# design.net
KiCad netlist of a schematic drawn in Altium Designer
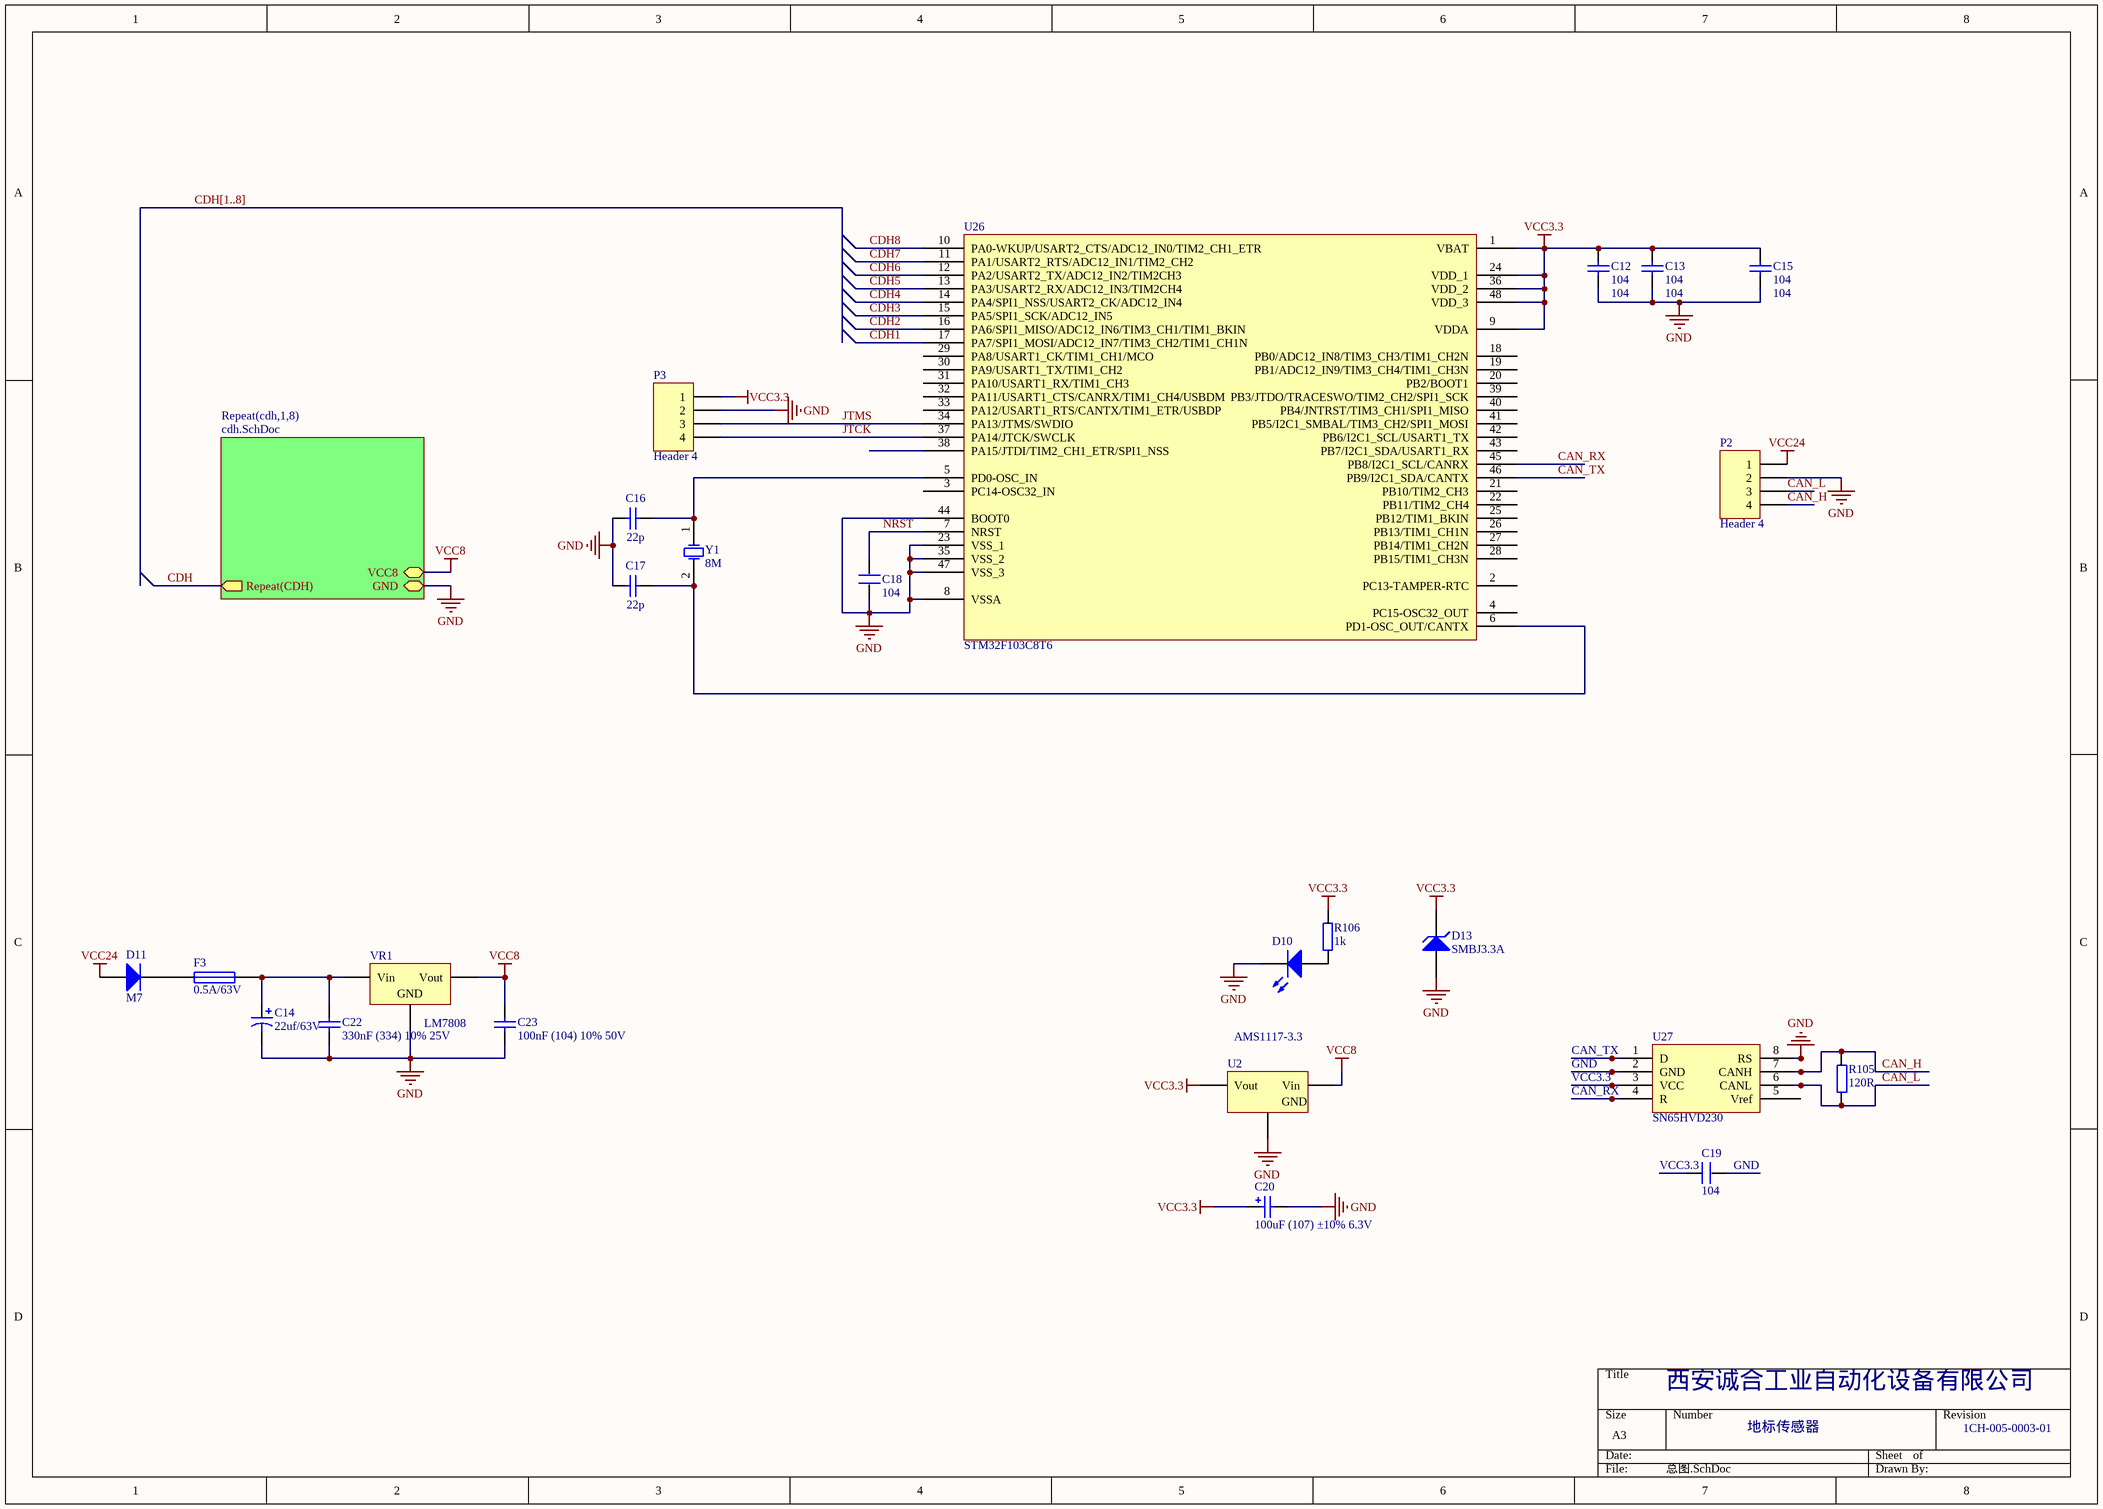
[diagram p0: 总图.SchDoc]

(export (version "E")
  (design (tool "Eeschema 10.0.6"))
  (components
    (comp (ref "C12")
      (value "104")
      (footprint "0603-CAP")
      (description "Capacitor")
      (fields (field (name "ALTIUM_VALUE") "104") (field (name "PUBLISHER") "Altium Limited"))
      (libsource (lib "Miscellaneous Devices") (part "Cap"))
    )
    (comp (ref "C13")
      (value "104")
      (footprint "0603-CAP")
      (description "Capacitor")
      (fields (field (name "ALTIUM_VALUE") "104") (field (name "PUBLISHER") "Altium Limited"))
      (libsource (lib "Miscellaneous Devices") (part "Cap"))
    )
    (comp (ref "C14")
      (value "22uf/63V")
      (footprint "CAP-6*12")
      (description "Polarized Capacitor (Surface Mount)")
      (fields (field (name "PUBLISHER") "Altium Limited"))
      (libsource (lib "Miscellaneous Devices") (part "Cap Pol3"))
    )
    (comp (ref "C15")
      (value "104")
      (footprint "0603-CAP")
      (description "Capacitor")
      (fields (field (name "ALTIUM_VALUE") "104") (field (name "PUBLISHER") "Altium Limited"))
      (libsource (lib "Miscellaneous Devices") (part "Cap"))
    )
    (comp (ref "C16")
      (value "22p")
      (footprint "0603-CAP")
      (description "Capacitor")
      (fields (field (name "PUBLISHER") "Altium Limited"))
      (libsource (lib "Miscellaneous Devices") (part "Cap"))
    )
    (comp (ref "C17")
      (value "22p")
      (footprint "0603-CAP")
      (description "Capacitor")
      (fields (field (name "PUBLISHER") "Altium Limited"))
      (libsource (lib "Miscellaneous Devices") (part "Cap"))
    )
    (comp (ref "C18")
      (value "104")
      (footprint "0603-CAP")
      (libsource (lib "Explorer STM32F407封装库") (part "C"))
    )
    (comp (ref "C19")
      (value "104")
      (footprint "0603-CAP")
      (libsource (lib "Explorer STM32F407封装库") (part "C_3"))
    )
    (comp (ref "C20")
      (value "100uF (107) ±10% 6.3V")
      (footprint "CASE-B_3528")
      (description "钽电容")
      (libsource (lib "Miscellaneous Devices LC") (part "3528 100uF (107) 10% 6.3V"))
    )
    (comp (ref "C22")
      (value "330nF (334) 10% 25V")
      (footprint "0603_C")
      (description "贴片电容")
      (libsource (lib "Miscellaneous Devices LC") (part "0603 330nF (334) 10% 25V"))
    )
    (comp (ref "C23")
      (value "100nF (104) 10% 50V")
      (footprint "0603_C")
      (description "贴片电容")
      (libsource (lib "Miscellaneous Devices LC") (part "0603 100nF (104) 10% 50V"))
    )
    (comp (ref "D10")
      (value "LED0")
      (footprint "LC-0805_LED_S1")
      (description "Typical INFRARED GaAs LED")
      (fields (field (name "PUBLISHER") "Altium Limited"))
      (libsource (lib "继电器板_1") (part "LED0"))
    )
    (comp (ref "D11")
      (value "M7")
      (footprint "SMA(DO-214AC)_S1")
      (description "二极管")
      (libsource (lib "Miscellaneous Devices LC") (part "SMA(DO-214AC) M7"))
    )
    (comp (ref "D13")
      (value "SMBJ3.3A")
      (footprint "SMB(DO-214AA)_S1")
      (description "Zener Diode")
      (fields (field (name "PUBLISHER") "Altium Limited"))
      (libsource (lib "Miscellaneous Devices") (part "D Zener"))
    )
    (comp (ref "F3")
      (value "0.5A/63V")
      (footprint "1206")
      (description "Fuse")
      (fields (field (name "PUBLISHER") "Altium Limited"))
      (libsource (lib "Miscellaneous Devices") (part "Fuse 1"))
    )
    (comp (ref "P2")
      (value "Header 4")
      (footprint "DZ-4-3.5")
      (description "Header, 4-Pin")
      (fields (field (name "PUBLISHER") "Altium Limited"))
      (libsource (lib "Miscellaneous Connectors") (part "Header 4"))
    )
    (comp (ref "P3")
      (value "Header 4")
      (footprint "HDR1X4")
      (description "Header, 4-Pin")
      (fields (field (name "PUBLISHER") "Altium Limited"))
      (libsource (lib "Miscellaneous Connectors") (part "Header 4"))
    )
    (comp (ref "R105")
      (value "120R")
      (footprint "0603")
      (libsource (lib "Explorer STM32F407封装库") (part "R_2"))
    )
    (comp (ref "R106") (value "1k") (footprint "0603") (libsource (lib "Explorer STM32F407封装库") (part "R_2")))
    (comp (ref "U2")
      (value "AMS1117-3.3")
      (footprint "SOT-223")
      (description "低压差线性稳压(LDO)")
      (libsource (lib "Miscellaneous Devices LC") (part "SOT-223 AMS1117-3.3"))
    )
    (comp (ref "U26")
      (value "STM32F103C8T6")
      (footprint "LC-LQFP-48")
      (libsource (lib "Schlib1") (part "stm32f103v8t6"))
    )
    (comp (ref "U27")
      (value "SN65HVD230")
      (footprint "SOIC-8_150mil")
      (description "CAN")
      (libsource (lib "Miscellaneous Devices LC") (part "CAN/SN65HVD230DR"))
    )
    (comp (ref "VR1")
      (value "LM7808")
      (footprint "LC-TO-263-2")
      (description "低压差线性稳压(LDO)")
      (libsource (lib "Miscellaneous Devices LC") (part "SOT-89 78L05G-AB3-R"))
    )
    (comp (ref "Y1")
      (value "8M")
      (footprint "XTAL_US1")
      (description "Crystal Oscillator")
      (fields (field (name "PUBLISHER") "Altium Limited"))
      (libsource (lib "Miscellaneous Devices") (part "XTAL"))
    )
  )
  (nets
    (net (code "1") (name "/CAN_H") (class "Default")
      (node (ref "P2") (pin "4") (pinfunction "4_4") (pintype "passive"))
      (node (ref "R105") (pin "2") (pintype "passive"))
      (node (ref "U27") (pin "7") (pinfunction "CANH_7") (pintype "passive"))
    )
    (net (code "2") (name "/CAN_L") (class "Default")
      (node (ref "P2") (pin "3") (pinfunction "3_3") (pintype "passive"))
      (node (ref "R105") (pin "1") (pintype "passive"))
      (node (ref "U27") (pin "6") (pinfunction "CANL_6") (pintype "passive"))
    )
    (net (code "3") (name "/CAN_RX") (class "Default")
      (node (ref "U26") (pin "45") (pinfunction "PB8/I2C1_SCL/CANRX_45") (pintype "passive"))
      (node (ref "U27") (pin "4") (pinfunction "R_4") (pintype "passive"))
    )
    (net (code "4") (name "/CAN_TX") (class "Default")
      (node (ref "U26") (pin "46") (pinfunction "PB9/I2C1_SDA/CANTX_46") (pintype "passive"))
      (node (ref "U27") (pin "1") (pinfunction "D_1") (pintype "passive"))
    )
    (net (code "6") (name "/CDH1") (class "Default")
      (node (ref "U26") (pin "17") (pinfunction "PA7/SPI1_MOSI/ADC12_IN7/TIM3_CH2/TIM1_CH1N_17") (pintype "passive"))
    )
    (net (code "7") (name "/CDH2") (class "Default")
      (node (ref "U26") (pin "16") (pinfunction "PA6/SPI1_MISO/ADC12_IN6/TIM3_CH1/TIM1_BKIN_16") (pintype "passive"))
    )
    (net (code "8") (name "/CDH3") (class "Default")
      (node (ref "U26") (pin "15") (pinfunction "PA5/SPI1_SCK/ADC12_IN5_15") (pintype "passive"))
    )
    (net (code "9") (name "/CDH4") (class "Default")
      (node (ref "U26") (pin "14") (pinfunction "PA4/SPI1_NSS/USART2_CK/ADC12_IN4_14") (pintype "passive"))
    )
    (net (code "10") (name "/CDH5") (class "Default")
      (node (ref "U26") (pin "13") (pinfunction "PA3/USART2_RX/ADC12_IN3/TIM2CH4_13") (pintype "passive"))
    )
    (net (code "11") (name "/CDH6") (class "Default")
      (node (ref "U26") (pin "12") (pinfunction "PA2/USART2_TX/ADC12_IN2/TIM2CH3_12") (pintype "passive"))
    )
    (net (code "12") (name "/CDH7") (class "Default")
      (node (ref "U26") (pin "11") (pinfunction "PA1/USART2_RTS/ADC12_IN1/TIM2_CH2_11") (pintype "passive"))
    )
    (net (code "13") (name "/CDH8") (class "Default")
      (node (ref "U26") (pin "10") (pinfunction "PA0-WKUP/USART2_CTS/ADC12_IN0/TIM2_CH1_ETR_10") (pintype "passive"))
    )
    (net (code "15") (name "/JTCK") (class "Default")
      (node (ref "P3") (pin "4") (pinfunction "4_4") (pintype "passive"))
      (node (ref "U26") (pin "37") (pinfunction "PA14/JTCK/SWCLK_37") (pintype "passive"))
    )
    (net (code "16") (name "/JTMS") (class "Default")
      (node (ref "P3") (pin "3") (pinfunction "3_3") (pintype "passive"))
      (node (ref "U26") (pin "34") (pinfunction "PA13/JTMS/SWDIO_34") (pintype "passive"))
    )
    (net (code "17") (name "/NRST") (class "Default")
      (node (ref "C18") (pin "2") (pintype "passive"))
      (node (ref "U26") (pin "7") (pinfunction "NRST_7") (pintype "passive"))
    )
    (net (code "18") (name "GND") (class "Default")
      (node (ref "C12") (pin "2") (pinfunction "2_2") (pintype "passive"))
      (node (ref "C13") (pin "2") (pinfunction "2_2") (pintype "passive"))
      (node (ref "C14") (pin "2") (pinfunction "2_2") (pintype "passive"))
      (node (ref "C15") (pin "2") (pinfunction "2_2") (pintype "passive"))
      (node (ref "C16") (pin "2") (pinfunction "2_2") (pintype "passive"))
      (node (ref "C17") (pin "2") (pinfunction "2_2") (pintype "passive"))
      (node (ref "C18") (pin "1") (pintype "passive"))
      (node (ref "C19") (pin "2") (pintype "passive"))
      (node (ref "C20") (pin "2") (pinfunction "2_2") (pintype "passive"))
      (node (ref "C22") (pin "1") (pinfunction "1_1") (pintype "passive"))
      (node (ref "C23") (pin "1") (pinfunction "1_1") (pintype "passive"))
      (node (ref "D10") (pin "K") (pinfunction "K_K") (pintype "passive"))
      (node (ref "D13") (pin "1") (pinfunction "A_1") (pintype "passive"))
      (node (ref "P2") (pin "2") (pinfunction "2_2") (pintype "passive"))
      (node (ref "P3") (pin "2") (pinfunction "2_2") (pintype "passive"))
      (node (ref "U2") (pin "1") (pinfunction "GND_1") (pintype "passive"))
      (node (ref "U26") (pin "23") (pinfunction "VSS_1_23") (pintype "passive"))
      (node (ref "U26") (pin "35") (pinfunction "VSS_2_35") (pintype "passive"))
      (node (ref "U26") (pin "44") (pinfunction "BOOT0_44") (pintype "passive"))
      (node (ref "U26") (pin "47") (pinfunction "VSS_3_47") (pintype "passive"))
      (node (ref "U26") (pin "8") (pinfunction "VSSA_8") (pintype "passive"))
      (node (ref "U27") (pin "2") (pinfunction "GND_2") (pintype "passive"))
      (node (ref "U27") (pin "8") (pinfunction "RS_8") (pintype "passive"))
      (node (ref "VR1") (pin "2") (pinfunction "GND_2") (pintype "passive"))
    )
    (net (code "19") (name "Net-(D10-PadA)") (class "Default")
      (node (ref "D10") (pin "A") (pinfunction "A_A") (pintype "passive"))
      (node (ref "R106") (pin "2") (pintype "passive"))
    )
    (net (code "20") (name "Net-(D11-K)") (class "Default")
      (node (ref "D11") (pin "2") (pinfunction "K_2") (pintype "passive"))
      (node (ref "F3") (pin "1") (pinfunction "1_1") (pintype "passive"))
    )
    (net (code "21") (name "Net-(U26-PD0-OSC_IN)") (class "Default")
      (node (ref "C16") (pin "1") (pinfunction "1_1") (pintype "passive"))
      (node (ref "U26") (pin "5") (pinfunction "PD0-OSC_IN_5") (pintype "passive"))
      (node (ref "Y1") (pin "1") (pinfunction "OSC1_1") (pintype "passive"))
    )
    (net (code "22") (name "Net-(U26-PD1-OSC_OUT{slash}CANTX)") (class "Default")
      (node (ref "C17") (pin "1") (pinfunction "1_1") (pintype "passive"))
      (node (ref "U26") (pin "6") (pinfunction "PD1-OSC_OUT/CANTX_6") (pintype "passive"))
      (node (ref "Y1") (pin "2") (pinfunction "OSC2_2") (pintype "passive"))
    )
    (net (code "23") (name "Net-(VR1-Vin)") (class "Default")
      (node (ref "C14") (pin "1") (pinfunction "1_1") (pintype "passive"))
      (node (ref "C22") (pin "2") (pinfunction "2_2") (pintype "passive"))
      (node (ref "F3") (pin "2") (pinfunction "2_2") (pintype "passive"))
      (node (ref "VR1") (pin "1") (pinfunction "Vin_1") (pintype "passive"))
    )
    (net (code "24") (name "VCC3.3") (class "Default")
      (node (ref "C12") (pin "1") (pinfunction "1_1") (pintype "passive"))
      (node (ref "C13") (pin "1") (pinfunction "1_1") (pintype "passive"))
      (node (ref "C15") (pin "1") (pinfunction "1_1") (pintype "passive"))
      (node (ref "C19") (pin "1") (pintype "passive"))
      (node (ref "C20") (pin "1") (pinfunction "1_1") (pintype "passive"))
      (node (ref "D13") (pin "2") (pinfunction "K_2") (pintype "passive"))
      (node (ref "P3") (pin "1") (pinfunction "1_1") (pintype "passive"))
      (node (ref "R106") (pin "1") (pintype "passive"))
      (node (ref "U2") (pin "2") (pinfunction "Vout_2") (pintype "passive"))
      (node (ref "U26") (pin "1") (pinfunction "VBAT_1") (pintype "passive"))
      (node (ref "U26") (pin "24") (pinfunction "VDD_1_24") (pintype "passive"))
      (node (ref "U26") (pin "36") (pinfunction "VDD_2_36") (pintype "passive"))
      (node (ref "U26") (pin "48") (pinfunction "VDD_3_48") (pintype "passive"))
      (node (ref "U26") (pin "9") (pinfunction "VDDA_9") (pintype "passive"))
      (node (ref "U27") (pin "3") (pinfunction "VCC_3") (pintype "passive"))
    )
    (net (code "25") (name "VCC8") (class "Default")
      (node (ref "C23") (pin "2") (pinfunction "2_2") (pintype "passive"))
      (node (ref "U2") (pin "3") (pinfunction "Vin_3") (pintype "passive"))
      (node (ref "VR1") (pin "3") (pinfunction "Vout_3") (pintype "passive"))
    )
    (net (code "26") (name "VCC24") (class "Default")
      (node (ref "D11") (pin "1") (pinfunction "A_1") (pintype "passive"))
      (node (ref "P2") (pin "1") (pinfunction "1_1") (pintype "passive"))
    )
    (net (code "27") (name "unconnected-(U26-PA8{slash}USART1_CK{slash}TIM1_CH1{slash}MCO-Pad29)") (class "Default")
      (node (ref "U26") (pin "29") (pinfunction "PA8/USART1_CK/TIM1_CH1/MCO_29") (pintype "passive"))
    )
    (net (code "28") (name "unconnected-(U26-PA9{slash}USART1_TX{slash}TIM1_CH2-Pad30)") (class "Default")
      (node (ref "U26") (pin "30") (pinfunction "PA9/USART1_TX/TIM1_CH2_30") (pintype "passive"))
    )
    (net (code "29") (name "unconnected-(U26-PA10{slash}USART1_RX{slash}TIM1_CH3-Pad31)") (class "Default")
      (node (ref "U26") (pin "31") (pinfunction "PA10/USART1_RX/TIM1_CH3_31") (pintype "passive"))
    )
    (net (code "30") (name "unconnected-(U26-PA11{slash}USART1_CTS{slash}CANRX{slash}TIM1_CH4{slash}USBDM-Pad32)") (class "Default")
      (node (ref "U26") (pin "32") (pinfunction "PA11/USART1_CTS/CANRX/TIM1_CH4/USBDM_32") (pintype "passive"))
    )
    (net (code "31") (name "unconnected-(U26-PA12{slash}USART1_RTS{slash}CANTX{slash}TIM1_ETR{slash}USBDP-Pad33)") (class "Default")
      (node (ref "U26") (pin "33") (pinfunction "PA12/USART1_RTS/CANTX/TIM1_ETR/USBDP_33") (pintype "passive"))
    )
    (net (code "32") (name "unconnected-(U26-PA15{slash}JTDI{slash}TIM2_CH1_ETR{slash}SPI1_NSS-Pad38)") (class "Default")
      (node (ref "U26") (pin "38") (pinfunction "PA15/JTDI/TIM2_CH1_ETR/SPI1_NSS_38") (pintype "passive"))
    )
    (net (code "33") (name "unconnected-(U26-PB0{slash}ADC12_IN8{slash}TIM3_CH3{slash}TIM1_CH2N-Pad18)") (class "Default")
      (node (ref "U26") (pin "18") (pinfunction "PB0/ADC12_IN8/TIM3_CH3/TIM1_CH2N_18") (pintype "passive"))
    )
    (net (code "34") (name "unconnected-(U26-PB1{slash}ADC12_IN9{slash}TIM3_CH4{slash}TIM1_CH3N-Pad19)") (class "Default")
      (node (ref "U26") (pin "19") (pinfunction "PB1/ADC12_IN9/TIM3_CH4/TIM1_CH3N_19") (pintype "passive"))
    )
    (net (code "35") (name "unconnected-(U26-PB2{slash}BOOT1-Pad20)") (class "Default")
      (node (ref "U26") (pin "20") (pinfunction "PB2/BOOT1_20") (pintype "passive"))
    )
    (net (code "36") (name "unconnected-(U26-PB3{slash}JTDO{slash}TRACESWO{slash}TIM2_CH2{slash}SPI1_SCK-Pad39)") (class "Default")
      (node (ref "U26") (pin "39") (pinfunction "PB3/JTDO/TRACESWO/TIM2_CH2/SPI1_SCK_39") (pintype "passive"))
    )
    (net (code "37") (name "unconnected-(U26-PB4{slash}JNTRST{slash}TIM3_CH1{slash}SPI1_MISO-Pad40)") (class "Default")
      (node (ref "U26") (pin "40") (pinfunction "PB4/JNTRST/TIM3_CH1/SPI1_MISO_40") (pintype "passive"))
    )
    (net (code "38") (name "unconnected-(U26-PB5{slash}I2C1_SMBAL{slash}TIM3_CH2{slash}SPI1_MOSI-Pad41)") (class "Default")
      (node (ref "U26") (pin "41") (pinfunction "PB5/I2C1_SMBAL/TIM3_CH2/SPI1_MOSI_41") (pintype "passive"))
    )
    (net (code "39") (name "unconnected-(U26-PB6{slash}I2C1_SCL{slash}USART1_TX-Pad42)") (class "Default")
      (node (ref "U26") (pin "42") (pinfunction "PB6/I2C1_SCL/USART1_TX_42") (pintype "passive"))
    )
    (net (code "40") (name "unconnected-(U26-PB7{slash}I2C1_SDA{slash}USART1_RX-Pad43)") (class "Default")
      (node (ref "U26") (pin "43") (pinfunction "PB7/I2C1_SDA/USART1_RX_43") (pintype "passive"))
    )
    (net (code "41") (name "unconnected-(U26-PB10{slash}TIM2_CH3-Pad21)") (class "Default")
      (node (ref "U26") (pin "21") (pinfunction "PB10/TIM2_CH3_21") (pintype "passive"))
    )
    (net (code "42") (name "unconnected-(U26-PB11{slash}TIM2_CH4-Pad22)") (class "Default")
      (node (ref "U26") (pin "22") (pinfunction "PB11/TIM2_CH4_22") (pintype "passive"))
    )
    (net (code "43") (name "unconnected-(U26-PB12{slash}TIM1_BKIN-Pad25)") (class "Default")
      (node (ref "U26") (pin "25") (pinfunction "PB12/TIM1_BKIN_25") (pintype "passive"))
    )
    (net (code "44") (name "unconnected-(U26-PB13{slash}TIM1_CH1N-Pad26)") (class "Default")
      (node (ref "U26") (pin "26") (pinfunction "PB13/TIM1_CH1N_26") (pintype "passive"))
    )
    (net (code "45") (name "unconnected-(U26-PB14{slash}TIM1_CH2N-Pad27)") (class "Default")
      (node (ref "U26") (pin "27") (pinfunction "PB14/TIM1_CH2N_27") (pintype "passive"))
    )
    (net (code "46") (name "unconnected-(U26-PB15{slash}TIM1_CH3N-Pad28)") (class "Default")
      (node (ref "U26") (pin "28") (pinfunction "PB15/TIM1_CH3N_28") (pintype "passive"))
    )
    (net (code "47") (name "unconnected-(U26-PC13-TAMPER-RTC-Pad2)") (class "Default")
      (node (ref "U26") (pin "2") (pinfunction "PC13-TAMPER-RTC_2") (pintype "passive"))
    )
    (net (code "48") (name "unconnected-(U26-PC14-OSC32_IN-Pad3)") (class "Default")
      (node (ref "U26") (pin "3") (pinfunction "PC14-OSC32_IN_3") (pintype "passive"))
    )
    (net (code "49") (name "unconnected-(U26-PC15-OSC32_OUT-Pad4)") (class "Default")
      (node (ref "U26") (pin "4") (pinfunction "PC15-OSC32_OUT_4") (pintype "passive"))
    )
    (net (code "50") (name "unconnected-(U27-Vref-Pad5)") (class "Default")
      (node (ref "U27") (pin "5") (pinfunction "Vref_5") (pintype "passive"))
    )
  )
)
